# WattMeter_v3_1.net
KiCad netlist of a schematic drawn in EAGLE
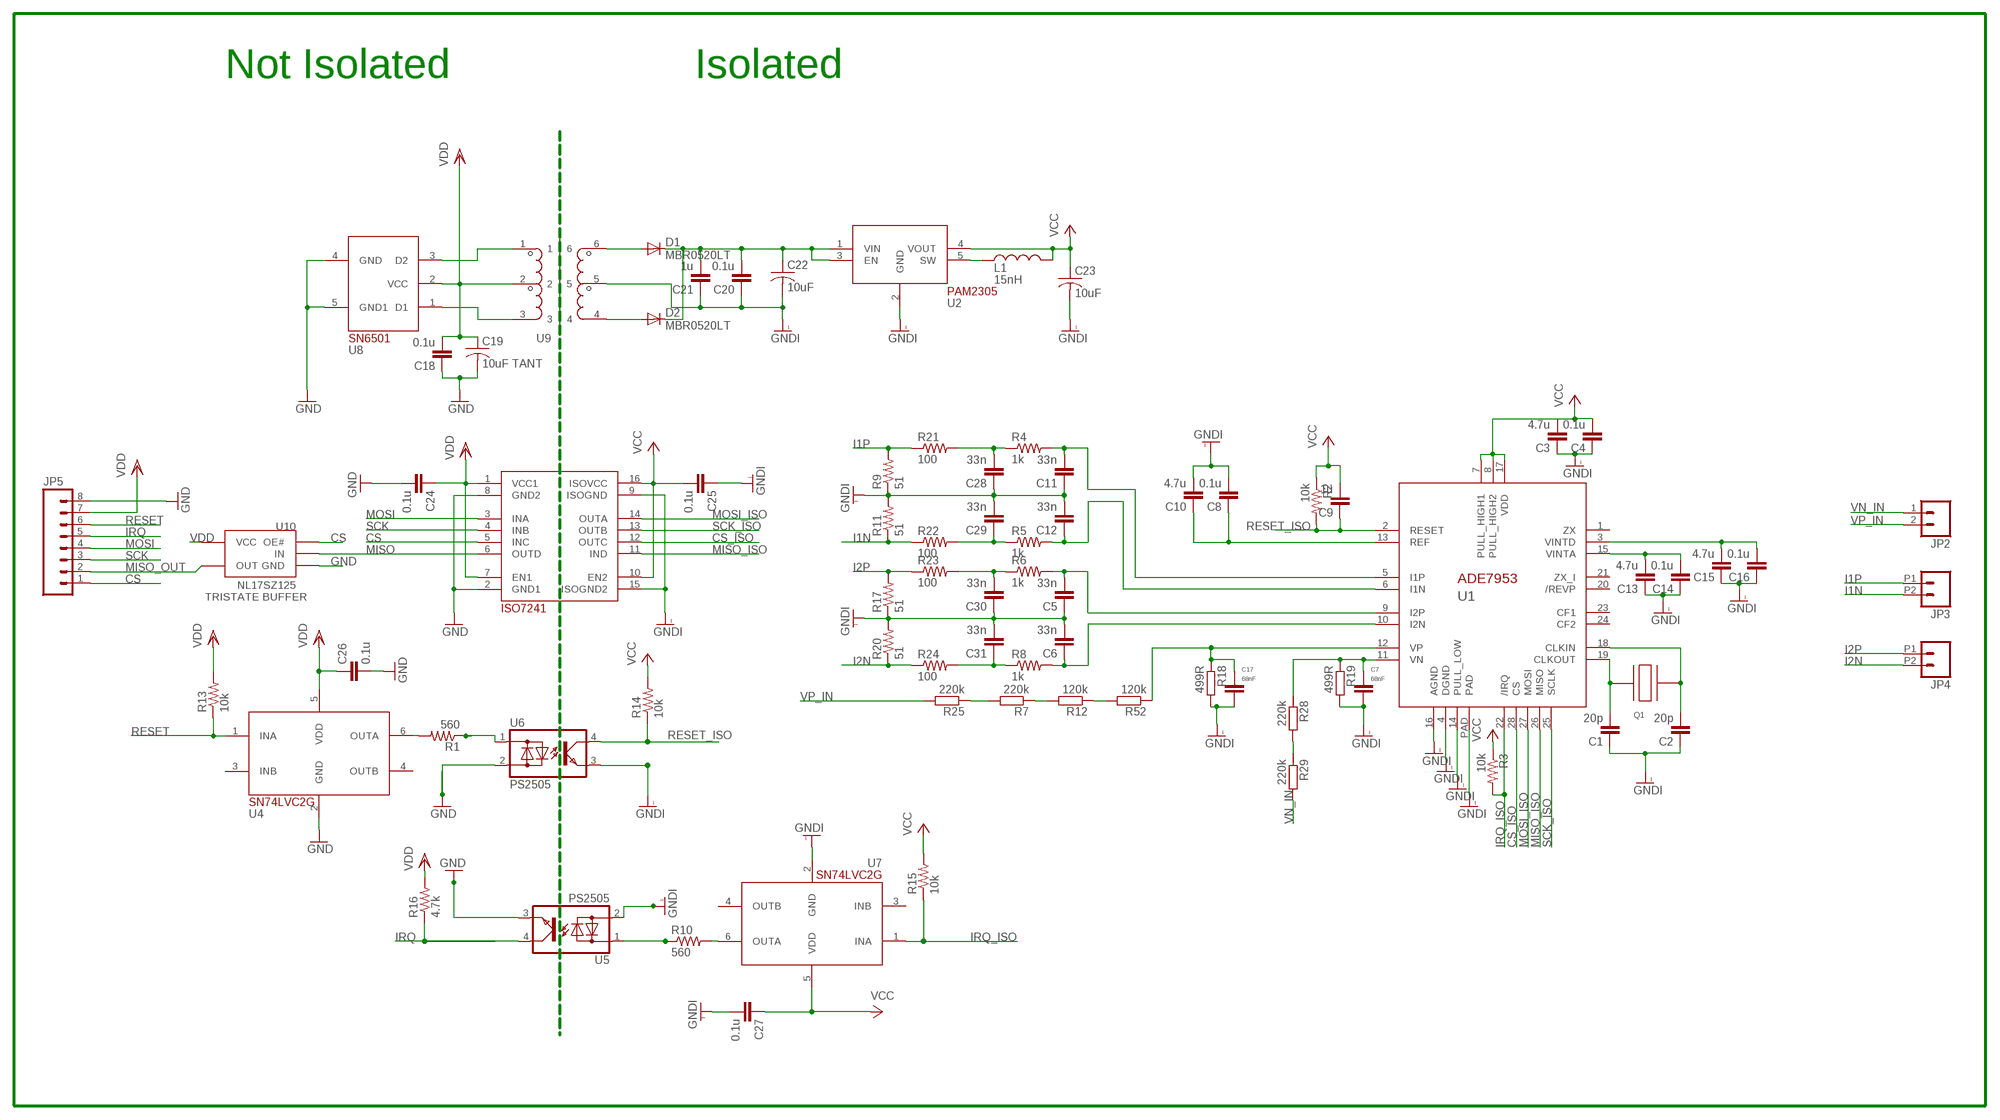
[diagram p0: schematic, sheet 1]

(export (version "E")
  (design (tool "Eeschema 10.0.6"))
  (components
    (comp (ref "C1")
      (value "20p")
      (footprint "eagle-import:0402-CAP")
      (libsource (lib "eagle-import") (part "0402-CAP"))
    )
    (comp (ref "C2")
      (value "20p")
      (footprint "eagle-import:0402-CAP")
      (libsource (lib "eagle-import") (part "0402-CAP"))
    )
    (comp (ref "C3")
      (value "4.7u")
      (footprint "eagle-import:0402-CAP")
      (libsource (lib "eagle-import") (part "0402-CAP"))
    )
    (comp (ref "C4")
      (value "0.1u")
      (footprint "eagle-import:0402-CAP")
      (libsource (lib "eagle-import") (part "0402-CAP"))
    )
    (comp (ref "C5")
      (value "33n")
      (footprint "eagle-import:0402-CAP")
      (libsource (lib "eagle-import") (part "0402-CAP"))
    )
    (comp (ref "C6")
      (value "33n")
      (footprint "eagle-import:0402-CAP")
      (libsource (lib "eagle-import") (part "0402-CAP"))
    )
    (comp (ref "C7")
      (value "68nF")
      (footprint "eagle-import:C0805K")
      (libsource (lib "eagle-import") (part "C-EUC0805K"))
    )
    (comp (ref "C8")
      (value "0.1u")
      (footprint "eagle-import:0402-CAP")
      (libsource (lib "eagle-import") (part "0402-CAP"))
    )
    (comp (ref "C9")
      (value "1u")
      (footprint "eagle-import:0402-CAP")
      (libsource (lib "eagle-import") (part "0402-CAP"))
    )
    (comp (ref "C10")
      (value "4.7u")
      (footprint "eagle-import:0402-CAP")
      (libsource (lib "eagle-import") (part "0402-CAP"))
    )
    (comp (ref "C11")
      (value "33n")
      (footprint "eagle-import:0402-CAP")
      (libsource (lib "eagle-import") (part "0402-CAP"))
    )
    (comp (ref "C12")
      (value "33n")
      (footprint "eagle-import:0402-CAP")
      (libsource (lib "eagle-import") (part "0402-CAP"))
    )
    (comp (ref "C13")
      (value "4.7u")
      (footprint "eagle-import:0402-CAP")
      (libsource (lib "eagle-import") (part "0402-CAP"))
    )
    (comp (ref "C14")
      (value "0.1u")
      (footprint "eagle-import:0402-CAP")
      (libsource (lib "eagle-import") (part "0402-CAP"))
    )
    (comp (ref "C15")
      (value "4.7u")
      (footprint "eagle-import:0402-CAP")
      (libsource (lib "eagle-import") (part "0402-CAP"))
    )
    (comp (ref "C16")
      (value "0.1u")
      (footprint "eagle-import:0402-CAP")
      (libsource (lib "eagle-import") (part "0402-CAP"))
    )
    (comp (ref "C17")
      (value "68nF")
      (footprint "eagle-import:C0805K")
      (libsource (lib "eagle-import") (part "C-EUC0805K"))
    )
    (comp (ref "C18")
      (value "0.1u")
      (footprint "eagle-import:0402-CAP")
      (libsource (lib "eagle-import") (part "0402-CAP"))
    )
    (comp (ref "C19")
      (value "10uF TANT")
      (footprint "eagle-import:C0603")
      (libsource (lib "eagle-import") (part "C-USC0603"))
    )
    (comp (ref "C20")
      (value "0.1u")
      (footprint "eagle-import:0402-CAP")
      (libsource (lib "eagle-import") (part "0402-CAP"))
    )
    (comp (ref "C21")
      (value "1u")
      (footprint "eagle-import:0402-CAP")
      (libsource (lib "eagle-import") (part "0402-CAP"))
    )
    (comp (ref "C22")
      (value "10uF")
      (footprint "eagle-import:C0603")
      (libsource (lib "eagle-import") (part "C-USC0603"))
    )
    (comp (ref "C23")
      (value "10uF")
      (footprint "eagle-import:C0603")
      (libsource (lib "eagle-import") (part "C-USC0603"))
    )
    (comp (ref "C24")
      (value "0.1u")
      (footprint "eagle-import:0402-CAP")
      (libsource (lib "eagle-import") (part "0402-CAP"))
    )
    (comp (ref "C25")
      (value "0.1u")
      (footprint "eagle-import:0402-CAP")
      (libsource (lib "eagle-import") (part "0402-CAP"))
    )
    (comp (ref "C26")
      (value "0.1u")
      (footprint "eagle-import:0402-CAP")
      (libsource (lib "eagle-import") (part "0402-CAP"))
    )
    (comp (ref "C27")
      (value "0.1u")
      (footprint "eagle-import:0402-CAP")
      (libsource (lib "eagle-import") (part "0402-CAP"))
    )
    (comp (ref "C28")
      (value "33n")
      (footprint "eagle-import:0402-CAP")
      (libsource (lib "eagle-import") (part "0402-CAP"))
    )
    (comp (ref "C29")
      (value "33n")
      (footprint "eagle-import:0402-CAP")
      (libsource (lib "eagle-import") (part "0402-CAP"))
    )
    (comp (ref "C30")
      (value "33n")
      (footprint "eagle-import:0402-CAP")
      (libsource (lib "eagle-import") (part "0402-CAP"))
    )
    (comp (ref "C31")
      (value "33n")
      (footprint "eagle-import:0402-CAP")
      (libsource (lib "eagle-import") (part "0402-CAP"))
    )
    (comp (ref "D1")
      (value "MBR0520LT")
      (footprint "eagle-import:SOD123")
      (libsource (lib "eagle-import") (part "MBR0520LT"))
    )
    (comp (ref "D2")
      (value "MBR0520LT")
      (footprint "eagle-import:SOD123")
      (libsource (lib "eagle-import") (part "MBR0520LT"))
    )
    (comp (ref "JP2")
      (value "M025MM")
      (footprint "eagle-import:SCREWTERMINAL-5MM-2")
      (libsource (lib "eagle-import") (part "M025MM"))
    )
    (comp (ref "JP3")
      (value "M022.54MM_SCREWTERM")
      (footprint "eagle-import:1X02_2.54_SCREWTERM")
      (libsource (lib "eagle-import") (part "M022.54MM_SCREWTERM"))
    )
    (comp (ref "JP4")
      (value "M022.54MM_SCREWTERM")
      (footprint "eagle-import:1X02_2.54_SCREWTERM")
      (libsource (lib "eagle-import") (part "M022.54MM_SCREWTERM"))
    )
    (comp (ref "JP5")
      (value "M08")
      (footprint "eagle-import:1X08_ROUND")
      (libsource (lib "eagle-import") (part "M08"))
    )
    (comp (ref "L1")
      (value "15nH")
      (footprint "eagle-import:0402-RES")
      (libsource (lib "eagle-import") (part "IND0402"))
    )
    (comp (ref "Q1")
      (value "QUARTZ_3.58M_2PIN")
      (footprint "eagle-import:HC-49S")
      (libsource (lib "eagle-import") (part "QUARTZ_3.58M_2PIN"))
    )
    (comp (ref "R1")
      (value "560")
      (footprint "eagle-import:0402-RES")
      (libsource (lib "eagle-import") (part "0402-RES"))
    )
    (comp (ref "R2")
      (value "10k")
      (footprint "eagle-import:0402-RES")
      (libsource (lib "eagle-import") (part "0402-RES"))
    )
    (comp (ref "R3")
      (value "10k")
      (footprint "eagle-import:0402-RES")
      (libsource (lib "eagle-import") (part "0402-RES"))
    )
    (comp (ref "R4")
      (value "1k")
      (footprint "eagle-import:0402-RES")
      (libsource (lib "eagle-import") (part "0402-RES"))
    )
    (comp (ref "R5")
      (value "1k")
      (footprint "eagle-import:0402-RES")
      (libsource (lib "eagle-import") (part "0402-RES"))
    )
    (comp (ref "R6")
      (value "1k")
      (footprint "eagle-import:0402-RES")
      (libsource (lib "eagle-import") (part "0402-RES"))
    )
    (comp (ref "R7")
      (value "220k")
      (footprint "eagle-import:R2010")
      (libsource (lib "eagle-import") (part "R-EU_R2010"))
    )
    (comp (ref "R8")
      (value "1k")
      (footprint "eagle-import:0402-RES")
      (libsource (lib "eagle-import") (part "0402-RES"))
    )
    (comp (ref "R9")
      (value "51")
      (footprint "eagle-import:0402-RES")
      (libsource (lib "eagle-import") (part "0402-RES"))
    )
    (comp (ref "R10")
      (value "560")
      (footprint "eagle-import:0402-RES")
      (libsource (lib "eagle-import") (part "0402-RES"))
    )
    (comp (ref "R11")
      (value "51")
      (footprint "eagle-import:0402-RES")
      (libsource (lib "eagle-import") (part "0402-RES"))
    )
    (comp (ref "R12")
      (value "120k")
      (footprint "eagle-import:M1206")
      (libsource (lib "eagle-import") (part "R-EU_M1206"))
    )
    (comp (ref "R13")
      (value "10k")
      (footprint "eagle-import:0402-RES")
      (libsource (lib "eagle-import") (part "0402-RES"))
    )
    (comp (ref "R14")
      (value "10k")
      (footprint "eagle-import:0402-RES")
      (libsource (lib "eagle-import") (part "0402-RES"))
    )
    (comp (ref "R15")
      (value "10k")
      (footprint "eagle-import:0402-RES")
      (libsource (lib "eagle-import") (part "0402-RES"))
    )
    (comp (ref "R16")
      (value "4.7k")
      (footprint "eagle-import:0402-RES")
      (libsource (lib "eagle-import") (part "0402-RES"))
    )
    (comp (ref "R17")
      (value "51")
      (footprint "eagle-import:0402-RES")
      (libsource (lib "eagle-import") (part "0402-RES"))
    )
    (comp (ref "R18")
      (value "499R")
      (footprint "eagle-import:C0805K@1")
      (libsource (lib "eagle-import") (part "R-EU_"))
    )
    (comp (ref "R19")
      (value "499R")
      (footprint "eagle-import:C0805K@1")
      (libsource (lib "eagle-import") (part "R-EU_"))
    )
    (comp (ref "R20")
      (value "51")
      (footprint "eagle-import:0402-RES")
      (libsource (lib "eagle-import") (part "0402-RES"))
    )
    (comp (ref "R21")
      (value "100")
      (footprint "eagle-import:0402-RES")
      (libsource (lib "eagle-import") (part "0402-RES"))
    )
    (comp (ref "R22")
      (value "100")
      (footprint "eagle-import:0402-RES")
      (libsource (lib "eagle-import") (part "0402-RES"))
    )
    (comp (ref "R23")
      (value "100")
      (footprint "eagle-import:0402-RES")
      (libsource (lib "eagle-import") (part "0402-RES"))
    )
    (comp (ref "R24")
      (value "100")
      (footprint "eagle-import:0402-RES")
      (libsource (lib "eagle-import") (part "0402-RES"))
    )
    (comp (ref "R25")
      (value "220k")
      (footprint "eagle-import:R2010")
      (libsource (lib "eagle-import") (part "R-EU_R2010"))
    )
    (comp (ref "R28")
      (value "220k")
      (footprint "eagle-import:R2010")
      (libsource (lib "eagle-import") (part "R-EU_R2010"))
    )
    (comp (ref "R29")
      (value "220k")
      (footprint "eagle-import:R2010")
      (libsource (lib "eagle-import") (part "R-EU_R2010"))
    )
    (comp (ref "R52")
      (value "120k")
      (footprint "eagle-import:M1206")
      (libsource (lib "eagle-import") (part "R-EU_M1206"))
    )
    (comp (ref "U1")
      (value "ADE7953")
      (footprint "eagle-import:28-WFQFN")
      (libsource (lib "eagle-import") (part "ADE7953"))
    )
    (comp (ref "U2")
      (value "PAM2305")
      (footprint "eagle-import:TSOT25")
      (libsource (lib "eagle-import") (part "PAM2305"))
    )
    (comp (ref "U3")
      (value "ISO7241")
      (footprint "eagle-import:16-SOIC")
      (libsource (lib "eagle-import") (part "ISO7241"))
    )
    (comp (ref "U4")
      (value "SN74LVC")
      (footprint "eagle-import:DCKT")
      (libsource (lib "eagle-import") (part "SN74LVC"))
    )
    (comp (ref "U5")
      (value "PS2505")
      (footprint "eagle-import:PS2505")
      (libsource (lib "eagle-import") (part "PS2505"))
    )
    (comp (ref "U6")
      (value "PS2505")
      (footprint "eagle-import:PS2505")
      (libsource (lib "eagle-import") (part "PS2505"))
    )
    (comp (ref "U7")
      (value "SN74LVC")
      (footprint "eagle-import:DCKT")
      (libsource (lib "eagle-import") (part "SN74LVC"))
    )
    (comp (ref "U8")
      (value "SN6501")
      (footprint "eagle-import:SOT-23-5")
      (libsource (lib "eagle-import") (part "SN6501"))
    )
    (comp (ref "U9")
      (value "TRANSFO_3.3")
      (footprint "eagle-import:TRANSFO_3.3")
      (libsource (lib "eagle-import") (part "TRANSFO_3.3"))
    )
    (comp (ref "U10")
      (value "BUFFER-NL17SZ125")
      (footprint "eagle-import:TSOP-5")
      (libsource (lib "eagle-import") (part "BUFFER-NL17SZ125"))
    )
  )
  (nets
    (net (code "1") (name "/CS") (class "Default")
      (node (ref "JP5") (pin "1") (pinfunction "1_1") (pintype "passive"))
      (node (ref "U10") (pin "1") (pinfunction "OE#_1") (pintype "bidirectional"))
      (node (ref "U3") (pin "5") (pinfunction "INC_5") (pintype "bidirectional"))
    )
    (net (code "2") (name "/CS_ISO") (class "Default")
      (node (ref "U1") (pin "28") (pinfunction "CS_28") (pintype "bidirectional"))
      (node (ref "U3") (pin "12") (pinfunction "OUTC_12") (pintype "bidirectional"))
    )
    (net (code "3") (name "/I1N") (class "Default")
      (node (ref "JP3") (pin "P2") (pinfunction "2_P2") (pintype "passive"))
      (node (ref "R11") (pin "1") (pinfunction "1_1") (pintype "passive"))
      (node (ref "R22") (pin "1") (pinfunction "1_1") (pintype "passive"))
    )
    (net (code "4") (name "/I1P") (class "Default")
      (node (ref "JP3") (pin "P1") (pinfunction "1_P1") (pintype "passive"))
      (node (ref "R21") (pin "1") (pinfunction "1_1") (pintype "passive"))
      (node (ref "R9") (pin "2") (pinfunction "2_2") (pintype "passive"))
    )
    (net (code "5") (name "/I2N") (class "Default")
      (node (ref "JP4") (pin "P2") (pinfunction "2_P2") (pintype "passive"))
      (node (ref "R20") (pin "1") (pinfunction "1_1") (pintype "passive"))
      (node (ref "R24") (pin "1") (pinfunction "1_1") (pintype "passive"))
    )
    (net (code "6") (name "/I2P") (class "Default")
      (node (ref "JP4") (pin "P1") (pinfunction "1_P1") (pintype "passive"))
      (node (ref "R17") (pin "2") (pinfunction "2_2") (pintype "passive"))
      (node (ref "R23") (pin "1") (pinfunction "1_1") (pintype "passive"))
    )
    (net (code "7") (name "/IRQ") (class "Default")
      (node (ref "JP5") (pin "5") (pinfunction "5_5") (pintype "passive"))
      (node (ref "R16") (pin "1") (pinfunction "1_1") (pintype "passive"))
      (node (ref "U5") (pin "4") (pinfunction "COLLERTOR_4") (pintype "passive"))
    )
    (net (code "8") (name "/IRQ_ISO") (class "Default")
      (node (ref "R15") (pin "1") (pinfunction "1_1") (pintype "passive"))
      (node (ref "R3") (pin "2") (pinfunction "2_2") (pintype "passive"))
      (node (ref "U1") (pin "22") (pinfunction "/IRQ_22") (pintype "bidirectional"))
      (node (ref "U7") (pin "1") (pinfunction "INA_1") (pintype "bidirectional"))
    )
    (net (code "9") (name "/MISO") (class "Default")
      (node (ref "U10") (pin "2") (pinfunction "IN_2") (pintype "bidirectional"))
      (node (ref "U3") (pin "6") (pinfunction "OUTD_6") (pintype "bidirectional"))
    )
    (net (code "10") (name "/MISO_ISO") (class "Default")
      (node (ref "U1") (pin "26") (pinfunction "MISO_26") (pintype "bidirectional"))
      (node (ref "U3") (pin "11") (pinfunction "IND_11") (pintype "bidirectional"))
    )
    (net (code "11") (name "/MISO_OUT") (class "Default")
      (node (ref "JP5") (pin "2") (pinfunction "2_2") (pintype "passive"))
      (node (ref "U10") (pin "4") (pinfunction "OUT_4") (pintype "bidirectional"))
    )
    (net (code "12") (name "/MOSI") (class "Default")
      (node (ref "JP5") (pin "4") (pinfunction "4_4") (pintype "passive"))
      (node (ref "U3") (pin "3") (pinfunction "INA_3") (pintype "bidirectional"))
    )
    (net (code "13") (name "/MOSI_ISO") (class "Default")
      (node (ref "U1") (pin "27") (pinfunction "MOSI_27") (pintype "bidirectional"))
      (node (ref "U3") (pin "14") (pinfunction "OUTA_14") (pintype "bidirectional"))
    )
    (net (code "14") (name "/RESET") (class "Default")
      (node (ref "JP5") (pin "6") (pinfunction "6_6") (pintype "passive"))
      (node (ref "R13") (pin "1") (pinfunction "1_1") (pintype "passive"))
      (node (ref "U4") (pin "1") (pinfunction "INA_1") (pintype "bidirectional"))
    )
    (net (code "15") (name "/RESET_ISO") (class "Default")
      (node (ref "C9") (pin "1") (pinfunction "1_1") (pintype "passive"))
      (node (ref "R14") (pin "1") (pinfunction "1_1") (pintype "passive"))
      (node (ref "R2") (pin "2") (pinfunction "2_2") (pintype "passive"))
      (node (ref "U1") (pin "2") (pinfunction "RESET_2") (pintype "bidirectional"))
      (node (ref "U6") (pin "4") (pinfunction "COLLERTOR_4") (pintype "passive"))
    )
    (net (code "16") (name "/SCK") (class "Default")
      (node (ref "JP5") (pin "3") (pinfunction "3_3") (pintype "passive"))
      (node (ref "U3") (pin "4") (pinfunction "INB_4") (pintype "bidirectional"))
    )
    (net (code "17") (name "/SCK_ISO") (class "Default")
      (node (ref "U1") (pin "25") (pinfunction "SCLK_25") (pintype "bidirectional"))
      (node (ref "U3") (pin "13") (pinfunction "OUTB_13") (pintype "bidirectional"))
    )
    (net (code "18") (name "/VN_IN") (class "Default")
      (node (ref "JP2") (pin "1") (pinfunction "1_1") (pintype "passive"))
      (node (ref "R29") (pin "2") (pinfunction "2_2") (pintype "passive"))
    )
    (net (code "19") (name "/VP_IN") (class "Default")
      (node (ref "JP2") (pin "2") (pinfunction "2_2") (pintype "passive"))
      (node (ref "R25") (pin "2") (pinfunction "2_2") (pintype "passive"))
    )
    (net (code "20") (name "GND") (class "Default")
      (node (ref "C18") (pin "1") (pinfunction "1_1") (pintype "passive"))
      (node (ref "C19") (pin "2") (pinfunction "2_2") (pintype "passive"))
      (node (ref "C24") (pin "2") (pinfunction "2_2") (pintype "passive"))
      (node (ref "C26") (pin "2") (pinfunction "2_2") (pintype "passive"))
      (node (ref "JP5") (pin "8") (pinfunction "8_8") (pintype "passive"))
      (node (ref "U10") (pin "3") (pinfunction "GND_3") (pintype "bidirectional"))
      (node (ref "U3") (pin "2") (pinfunction "GND1_2") (pintype "bidirectional"))
      (node (ref "U3") (pin "8") (pinfunction "GND2_8") (pintype "bidirectional"))
      (node (ref "U4") (pin "2") (pinfunction "GND_2") (pintype "bidirectional"))
      (node (ref "U5") (pin "3") (pinfunction "EMITTER_3") (pintype "passive"))
      (node (ref "U6") (pin "2") (pinfunction "CATHODE_2") (pintype "passive"))
      (node (ref "U8") (pin "4") (pinfunction "GND_4") (pintype "bidirectional"))
      (node (ref "U8") (pin "5") (pinfunction "GND1_5") (pintype "bidirectional"))
    )
    (net (code "21") (name "GNDI") (class "Default")
      (node (ref "C1") (pin "1") (pinfunction "1_1") (pintype "passive"))
      (node (ref "C10") (pin "2") (pinfunction "2_2") (pintype "passive"))
      (node (ref "C11") (pin "1") (pinfunction "1_1") (pintype "passive"))
      (node (ref "C12") (pin "2") (pinfunction "2_2") (pintype "passive"))
      (node (ref "C13") (pin "1") (pinfunction "1_1") (pintype "passive"))
      (node (ref "C14") (pin "1") (pinfunction "1_1") (pintype "passive"))
      (node (ref "C15") (pin "1") (pinfunction "1_1") (pintype "passive"))
      (node (ref "C16") (pin "1") (pinfunction "1_1") (pintype "passive"))
      (node (ref "C17") (pin "2") (pinfunction "2_2") (pintype "passive"))
      (node (ref "C2") (pin "1") (pinfunction "1_1") (pintype "passive"))
      (node (ref "C20") (pin "1") (pinfunction "1_1") (pintype "passive"))
      (node (ref "C21") (pin "1") (pinfunction "1_1") (pintype "passive"))
      (node (ref "C22") (pin "2") (pinfunction "2_2") (pintype "passive"))
      (node (ref "C23") (pin "2") (pinfunction "2_2") (pintype "passive"))
      (node (ref "C25") (pin "1") (pinfunction "1_1") (pintype "passive"))
      (node (ref "C27") (pin "2") (pinfunction "2_2") (pintype "passive"))
      (node (ref "C28") (pin "1") (pinfunction "1_1") (pintype "passive"))
      (node (ref "C29") (pin "2") (pinfunction "2_2") (pintype "passive"))
      (node (ref "C3") (pin "1") (pinfunction "1_1") (pintype "passive"))
      (node (ref "C30") (pin "1") (pinfunction "1_1") (pintype "passive"))
      (node (ref "C31") (pin "2") (pinfunction "2_2") (pintype "passive"))
      (node (ref "C4") (pin "1") (pinfunction "1_1") (pintype "passive"))
      (node (ref "C5") (pin "1") (pinfunction "1_1") (pintype "passive"))
      (node (ref "C6") (pin "2") (pinfunction "2_2") (pintype "passive"))
      (node (ref "C7") (pin "2") (pinfunction "2_2") (pintype "passive"))
      (node (ref "C8") (pin "2") (pinfunction "2_2") (pintype "passive"))
      (node (ref "R11") (pin "2") (pinfunction "2_2") (pintype "passive"))
      (node (ref "R17") (pin "1") (pinfunction "1_1") (pintype "passive"))
      (node (ref "R18") (pin "2") (pinfunction "2_2") (pintype "passive"))
      (node (ref "R19") (pin "2") (pinfunction "2_2") (pintype "passive"))
      (node (ref "R20") (pin "2") (pinfunction "2_2") (pintype "passive"))
      (node (ref "R9") (pin "1") (pinfunction "1_1") (pintype "passive"))
      (node (ref "U1") (pin "14") (pinfunction "PULL_LOW_14") (pintype "bidirectional"))
      (node (ref "U1") (pin "16") (pinfunction "AGND_16") (pintype "bidirectional"))
      (node (ref "U1") (pin "4") (pinfunction "DGND_4") (pintype "bidirectional"))
      (node (ref "U1") (pin "PAD") (pinfunction "PAD_PAD") (pintype "bidirectional"))
      (node (ref "U2") (pin "2") (pinfunction "GND_2") (pintype "bidirectional"))
      (node (ref "U3") (pin "15") (pinfunction "ISOGND2_15") (pintype "bidirectional"))
      (node (ref "U3") (pin "9") (pinfunction "ISOGND_9") (pintype "bidirectional"))
      (node (ref "U5") (pin "2") (pinfunction "CATHODE_2") (pintype "passive"))
      (node (ref "U6") (pin "3") (pinfunction "EMITTER_3") (pintype "passive"))
      (node (ref "U7") (pin "2") (pinfunction "GND_2") (pintype "bidirectional"))
      (node (ref "U9") (pin "5") (pinfunction "5_5") (pintype "bidirectional"))
    )
    (net (code "22") (name "Net-(C28-Pad2)") (class "Default")
      (node (ref "C28") (pin "2") (pinfunction "2_2") (pintype "passive"))
      (node (ref "R21") (pin "2") (pinfunction "2_2") (pintype "passive"))
      (node (ref "R4") (pin "1") (pinfunction "1_1") (pintype "passive"))
    )
    (net (code "23") (name "Net-(C29-Pad1)") (class "Default")
      (node (ref "C29") (pin "1") (pinfunction "1_1") (pintype "passive"))
      (node (ref "R22") (pin "2") (pinfunction "2_2") (pintype "passive"))
      (node (ref "R5") (pin "1") (pinfunction "1_1") (pintype "passive"))
    )
    (net (code "24") (name "Net-(C30-Pad2)") (class "Default")
      (node (ref "C30") (pin "2") (pinfunction "2_2") (pintype "passive"))
      (node (ref "R23") (pin "2") (pinfunction "2_2") (pintype "passive"))
      (node (ref "R6") (pin "1") (pinfunction "1_1") (pintype "passive"))
    )
    (net (code "25") (name "Net-(C31-Pad1)") (class "Default")
      (node (ref "C31") (pin "1") (pinfunction "1_1") (pintype "passive"))
      (node (ref "R24") (pin "2") (pinfunction "2_2") (pintype "passive"))
      (node (ref "R8") (pin "1") (pinfunction "1_1") (pintype "passive"))
    )
    (net (code "26") (name "Net-(D1-PadA)") (class "Default")
      (node (ref "D1") (pin "A") (pinfunction "A_A") (pintype "passive"))
      (node (ref "U9") (pin "6") (pinfunction "6_6") (pintype "bidirectional"))
    )
    (net (code "27") (name "Net-(D2-PadA)") (class "Default")
      (node (ref "D2") (pin "A") (pinfunction "A_A") (pintype "passive"))
      (node (ref "U9") (pin "4") (pinfunction "4_4") (pintype "bidirectional"))
    )
    (net (code "28") (name "Net-(R12-Pad1)") (class "Default")
      (node (ref "R12") (pin "1") (pinfunction "1_1") (pintype "passive"))
      (node (ref "R52") (pin "2") (pinfunction "2_2") (pintype "passive"))
    )
    (net (code "29") (name "Net-(R12-Pad2)") (class "Default")
      (node (ref "R12") (pin "2") (pinfunction "2_2") (pintype "passive"))
      (node (ref "R7") (pin "1") (pinfunction "1_1") (pintype "passive"))
    )
    (net (code "30") (name "Net-(R25-Pad1)") (class "Default")
      (node (ref "R25") (pin "1") (pinfunction "1_1") (pintype "passive"))
      (node (ref "R7") (pin "2") (pinfunction "2_2") (pintype "passive"))
    )
    (net (code "31") (name "Net-(R28-Pad2)") (class "Default")
      (node (ref "R28") (pin "2") (pinfunction "2_2") (pintype "passive"))
      (node (ref "R29") (pin "1") (pinfunction "1_1") (pintype "passive"))
    )
    (net (code "32") (name "Net-(U1-CLKIN)") (class "Default")
      (node (ref "C2") (pin "2") (pinfunction "2_2") (pintype "passive"))
      (node (ref "Q1") (pin "2") (pinfunction "2_2") (pintype "bidirectional"))
      (node (ref "U1") (pin "18") (pinfunction "CLKIN_18") (pintype "bidirectional"))
    )
    (net (code "33") (name "Net-(U1-CLKOUT)") (class "Default")
      (node (ref "C1") (pin "2") (pinfunction "2_2") (pintype "passive"))
      (node (ref "Q1") (pin "1") (pinfunction "1_1") (pintype "bidirectional"))
      (node (ref "U1") (pin "19") (pinfunction "CLKOUT_19") (pintype "bidirectional"))
    )
    (net (code "34") (name "Net-(U1-I1N)") (class "Default")
      (node (ref "C12") (pin "1") (pinfunction "1_1") (pintype "passive"))
      (node (ref "R5") (pin "2") (pinfunction "2_2") (pintype "passive"))
      (node (ref "U1") (pin "6") (pinfunction "I1N_6") (pintype "bidirectional"))
    )
    (net (code "35") (name "Net-(U1-I1P)") (class "Default")
      (node (ref "C11") (pin "2") (pinfunction "2_2") (pintype "passive"))
      (node (ref "R4") (pin "2") (pinfunction "2_2") (pintype "passive"))
      (node (ref "U1") (pin "5") (pinfunction "I1P_5") (pintype "bidirectional"))
    )
    (net (code "36") (name "Net-(U1-I2N)") (class "Default")
      (node (ref "C6") (pin "1") (pinfunction "1_1") (pintype "passive"))
      (node (ref "R8") (pin "2") (pinfunction "2_2") (pintype "passive"))
      (node (ref "U1") (pin "10") (pinfunction "I2N_10") (pintype "bidirectional"))
    )
    (net (code "37") (name "Net-(U1-I2P)") (class "Default")
      (node (ref "C5") (pin "2") (pinfunction "2_2") (pintype "passive"))
      (node (ref "R6") (pin "2") (pinfunction "2_2") (pintype "passive"))
      (node (ref "U1") (pin "9") (pinfunction "I2P_9") (pintype "bidirectional"))
    )
    (net (code "38") (name "Net-(U1-REF)") (class "Default")
      (node (ref "C10") (pin "1") (pinfunction "1_1") (pintype "passive"))
      (node (ref "C8") (pin "1") (pinfunction "1_1") (pintype "passive"))
      (node (ref "U1") (pin "13") (pinfunction "REF_13") (pintype "bidirectional"))
    )
    (net (code "39") (name "Net-(U1-VINTA)") (class "Default")
      (node (ref "C13") (pin "2") (pinfunction "2_2") (pintype "passive"))
      (node (ref "C14") (pin "2") (pinfunction "2_2") (pintype "passive"))
      (node (ref "U1") (pin "15") (pinfunction "VINTA_15") (pintype "bidirectional"))
    )
    (net (code "40") (name "Net-(U1-VINTD)") (class "Default")
      (node (ref "C15") (pin "2") (pinfunction "2_2") (pintype "passive"))
      (node (ref "C16") (pin "2") (pinfunction "2_2") (pintype "passive"))
      (node (ref "U1") (pin "3") (pinfunction "VINTD_3") (pintype "bidirectional"))
    )
    (net (code "41") (name "Net-(U1-VN)") (class "Default")
      (node (ref "C7") (pin "1") (pinfunction "1_1") (pintype "passive"))
      (node (ref "R19") (pin "1") (pinfunction "1_1") (pintype "passive"))
      (node (ref "R28") (pin "1") (pinfunction "1_1") (pintype "passive"))
      (node (ref "U1") (pin "11") (pinfunction "VN_11") (pintype "bidirectional"))
    )
    (net (code "42") (name "Net-(U1-VP)") (class "Default")
      (node (ref "C17") (pin "1") (pinfunction "1_1") (pintype "passive"))
      (node (ref "R18") (pin "1") (pinfunction "1_1") (pintype "passive"))
      (node (ref "R52") (pin "1") (pinfunction "1_1") (pintype "passive"))
      (node (ref "U1") (pin "12") (pinfunction "VP_12") (pintype "bidirectional"))
    )
    (net (code "43") (name "Net-(U2-EN)") (class "Default")
      (node (ref "C20") (pin "2") (pinfunction "2_2") (pintype "passive"))
      (node (ref "C21") (pin "2") (pinfunction "2_2") (pintype "passive"))
      (node (ref "C22") (pin "1") (pinfunction "1_1") (pintype "passive"))
      (node (ref "D1") (pin "C") (pinfunction "C_C") (pintype "passive"))
      (node (ref "D2") (pin "C") (pinfunction "C_C") (pintype "passive"))
      (node (ref "U2") (pin "1") (pinfunction "VIN_1") (pintype "bidirectional"))
      (node (ref "U2") (pin "3") (pinfunction "EN_3") (pintype "bidirectional"))
    )
    (net (code "44") (name "Net-(U2-SW)") (class "Default")
      (node (ref "L1") (pin "1") (pinfunction "1_1") (pintype "bidirectional"))
      (node (ref "U2") (pin "5") (pinfunction "SW_5") (pintype "bidirectional"))
    )
    (net (code "45") (name "Net-(U4-OUTA)") (class "Default")
      (node (ref "R1") (pin "2") (pinfunction "2_2") (pintype "passive"))
      (node (ref "U4") (pin "6") (pinfunction "OUTA_6") (pintype "bidirectional"))
    )
    (net (code "46") (name "Net-(U5-ANODE)") (class "Default")
      (node (ref "R10") (pin "1") (pinfunction "1_1") (pintype "passive"))
      (node (ref "U5") (pin "1") (pinfunction "ANODE_1") (pintype "passive"))
    )
    (net (code "47") (name "Net-(U6-ANODE)") (class "Default")
      (node (ref "R1") (pin "1") (pinfunction "1_1") (pintype "passive"))
      (node (ref "U6") (pin "1") (pinfunction "ANODE_1") (pintype "passive"))
    )
    (net (code "48") (name "Net-(U7-OUTA)") (class "Default")
      (node (ref "R10") (pin "2") (pinfunction "2_2") (pintype "passive"))
      (node (ref "U7") (pin "6") (pinfunction "OUTA_6") (pintype "bidirectional"))
    )
    (net (code "49") (name "Net-(U8-D1)") (class "Default")
      (node (ref "U8") (pin "1") (pinfunction "D1_1") (pintype "bidirectional"))
      (node (ref "U9") (pin "3") (pinfunction "3_3") (pintype "bidirectional"))
    )
    (net (code "50") (name "Net-(U8-D2)") (class "Default")
      (node (ref "U8") (pin "3") (pinfunction "D2_3") (pintype "bidirectional"))
      (node (ref "U9") (pin "1") (pinfunction "1_1") (pintype "bidirectional"))
    )
    (net (code "51") (name "VCC") (class "Default")
      (node (ref "C23") (pin "1") (pinfunction "1_1") (pintype "passive"))
      (node (ref "C25") (pin "2") (pinfunction "2_2") (pintype "passive"))
      (node (ref "C27") (pin "1") (pinfunction "1_1") (pintype "passive"))
      (node (ref "C3") (pin "2") (pinfunction "2_2") (pintype "passive"))
      (node (ref "C4") (pin "2") (pinfunction "2_2") (pintype "passive"))
      (node (ref "C9") (pin "2") (pinfunction "2_2") (pintype "passive"))
      (node (ref "L1") (pin "2") (pinfunction "2_2") (pintype "bidirectional"))
      (node (ref "R14") (pin "2") (pinfunction "2_2") (pintype "passive"))
      (node (ref "R15") (pin "2") (pinfunction "2_2") (pintype "passive"))
      (node (ref "R2") (pin "1") (pinfunction "1_1") (pintype "passive"))
      (node (ref "R3") (pin "1") (pinfunction "1_1") (pintype "passive"))
      (node (ref "U1") (pin "17") (pinfunction "VDD_17") (pintype "bidirectional"))
      (node (ref "U1") (pin "7") (pinfunction "PULL_HIGH1_7") (pintype "bidirectional"))
      (node (ref "U1") (pin "8") (pinfunction "PULL_HIGH2_8") (pintype "bidirectional"))
      (node (ref "U2") (pin "4") (pinfunction "VOUT_4") (pintype "bidirectional"))
      (node (ref "U3") (pin "10") (pinfunction "EN2_10") (pintype "bidirectional"))
      (node (ref "U3") (pin "16") (pinfunction "ISOVCC_16") (pintype "bidirectional"))
      (node (ref "U7") (pin "5") (pinfunction "VDD_5") (pintype "bidirectional"))
    )
    (net (code "52") (name "VDD") (class "Default")
      (node (ref "C18") (pin "2") (pinfunction "2_2") (pintype "passive"))
      (node (ref "C19") (pin "1") (pinfunction "1_1") (pintype "passive"))
      (node (ref "C24") (pin "1") (pinfunction "1_1") (pintype "passive"))
      (node (ref "C26") (pin "1") (pinfunction "1_1") (pintype "passive"))
      (node (ref "JP5") (pin "7") (pinfunction "7_7") (pintype "passive"))
      (node (ref "R13") (pin "2") (pinfunction "2_2") (pintype "passive"))
      (node (ref "R16") (pin "2") (pinfunction "2_2") (pintype "passive"))
      (node (ref "U10") (pin "5") (pinfunction "VCC_5") (pintype "bidirectional"))
      (node (ref "U3") (pin "1") (pinfunction "VCC1_1") (pintype "bidirectional"))
      (node (ref "U3") (pin "7") (pinfunction "EN1_7") (pintype "bidirectional"))
      (node (ref "U4") (pin "5") (pinfunction "VDD_5") (pintype "bidirectional"))
      (node (ref "U8") (pin "2") (pinfunction "VCC_2") (pintype "bidirectional"))
      (node (ref "U9") (pin "2") (pinfunction "2_2") (pintype "bidirectional"))
    )
    (net (code "53") (name "unconnected-(U1-CF1-Pad23)") (class "Default")
      (node (ref "U1") (pin "23") (pinfunction "CF1_23") (pintype "bidirectional"))
    )
    (net (code "54") (name "unconnected-(U1-CF2-Pad24)") (class "Default")
      (node (ref "U1") (pin "24") (pinfunction "CF2_24") (pintype "bidirectional"))
    )
    (net (code "55") (name "unconnected-(U1-ZX-Pad1)") (class "Default")
      (node (ref "U1") (pin "1") (pinfunction "ZX_1") (pintype "bidirectional"))
    )
    (net (code "56") (name "unconnected-(U1-ZX_I-Pad21)") (class "Default")
      (node (ref "U1") (pin "21") (pinfunction "ZX_I_21") (pintype "bidirectional"))
    )
    (net (code "57") (name "unconnected-(U1-{slash}REVP-Pad20)") (class "Default")
      (node (ref "U1") (pin "20") (pinfunction "/REVP_20") (pintype "bidirectional"))
    )
    (net (code "58") (name "unconnected-(U4-INB-Pad3)") (class "Default")
      (node (ref "U4") (pin "3") (pinfunction "INB_3") (pintype "bidirectional"))
    )
    (net (code "59") (name "unconnected-(U4-OUTB-Pad4)") (class "Default")
      (node (ref "U4") (pin "4") (pinfunction "OUTB_4") (pintype "bidirectional"))
    )
    (net (code "60") (name "unconnected-(U7-INB-Pad3)") (class "Default")
      (node (ref "U7") (pin "3") (pinfunction "INB_3") (pintype "bidirectional"))
    )
    (net (code "61") (name "unconnected-(U7-OUTB-Pad4)") (class "Default")
      (node (ref "U7") (pin "4") (pinfunction "OUTB_4") (pintype "bidirectional"))
    )
  )
)
